# PCB_Timbangan.net
KiCad netlist of a schematic drawn in EasyEDA
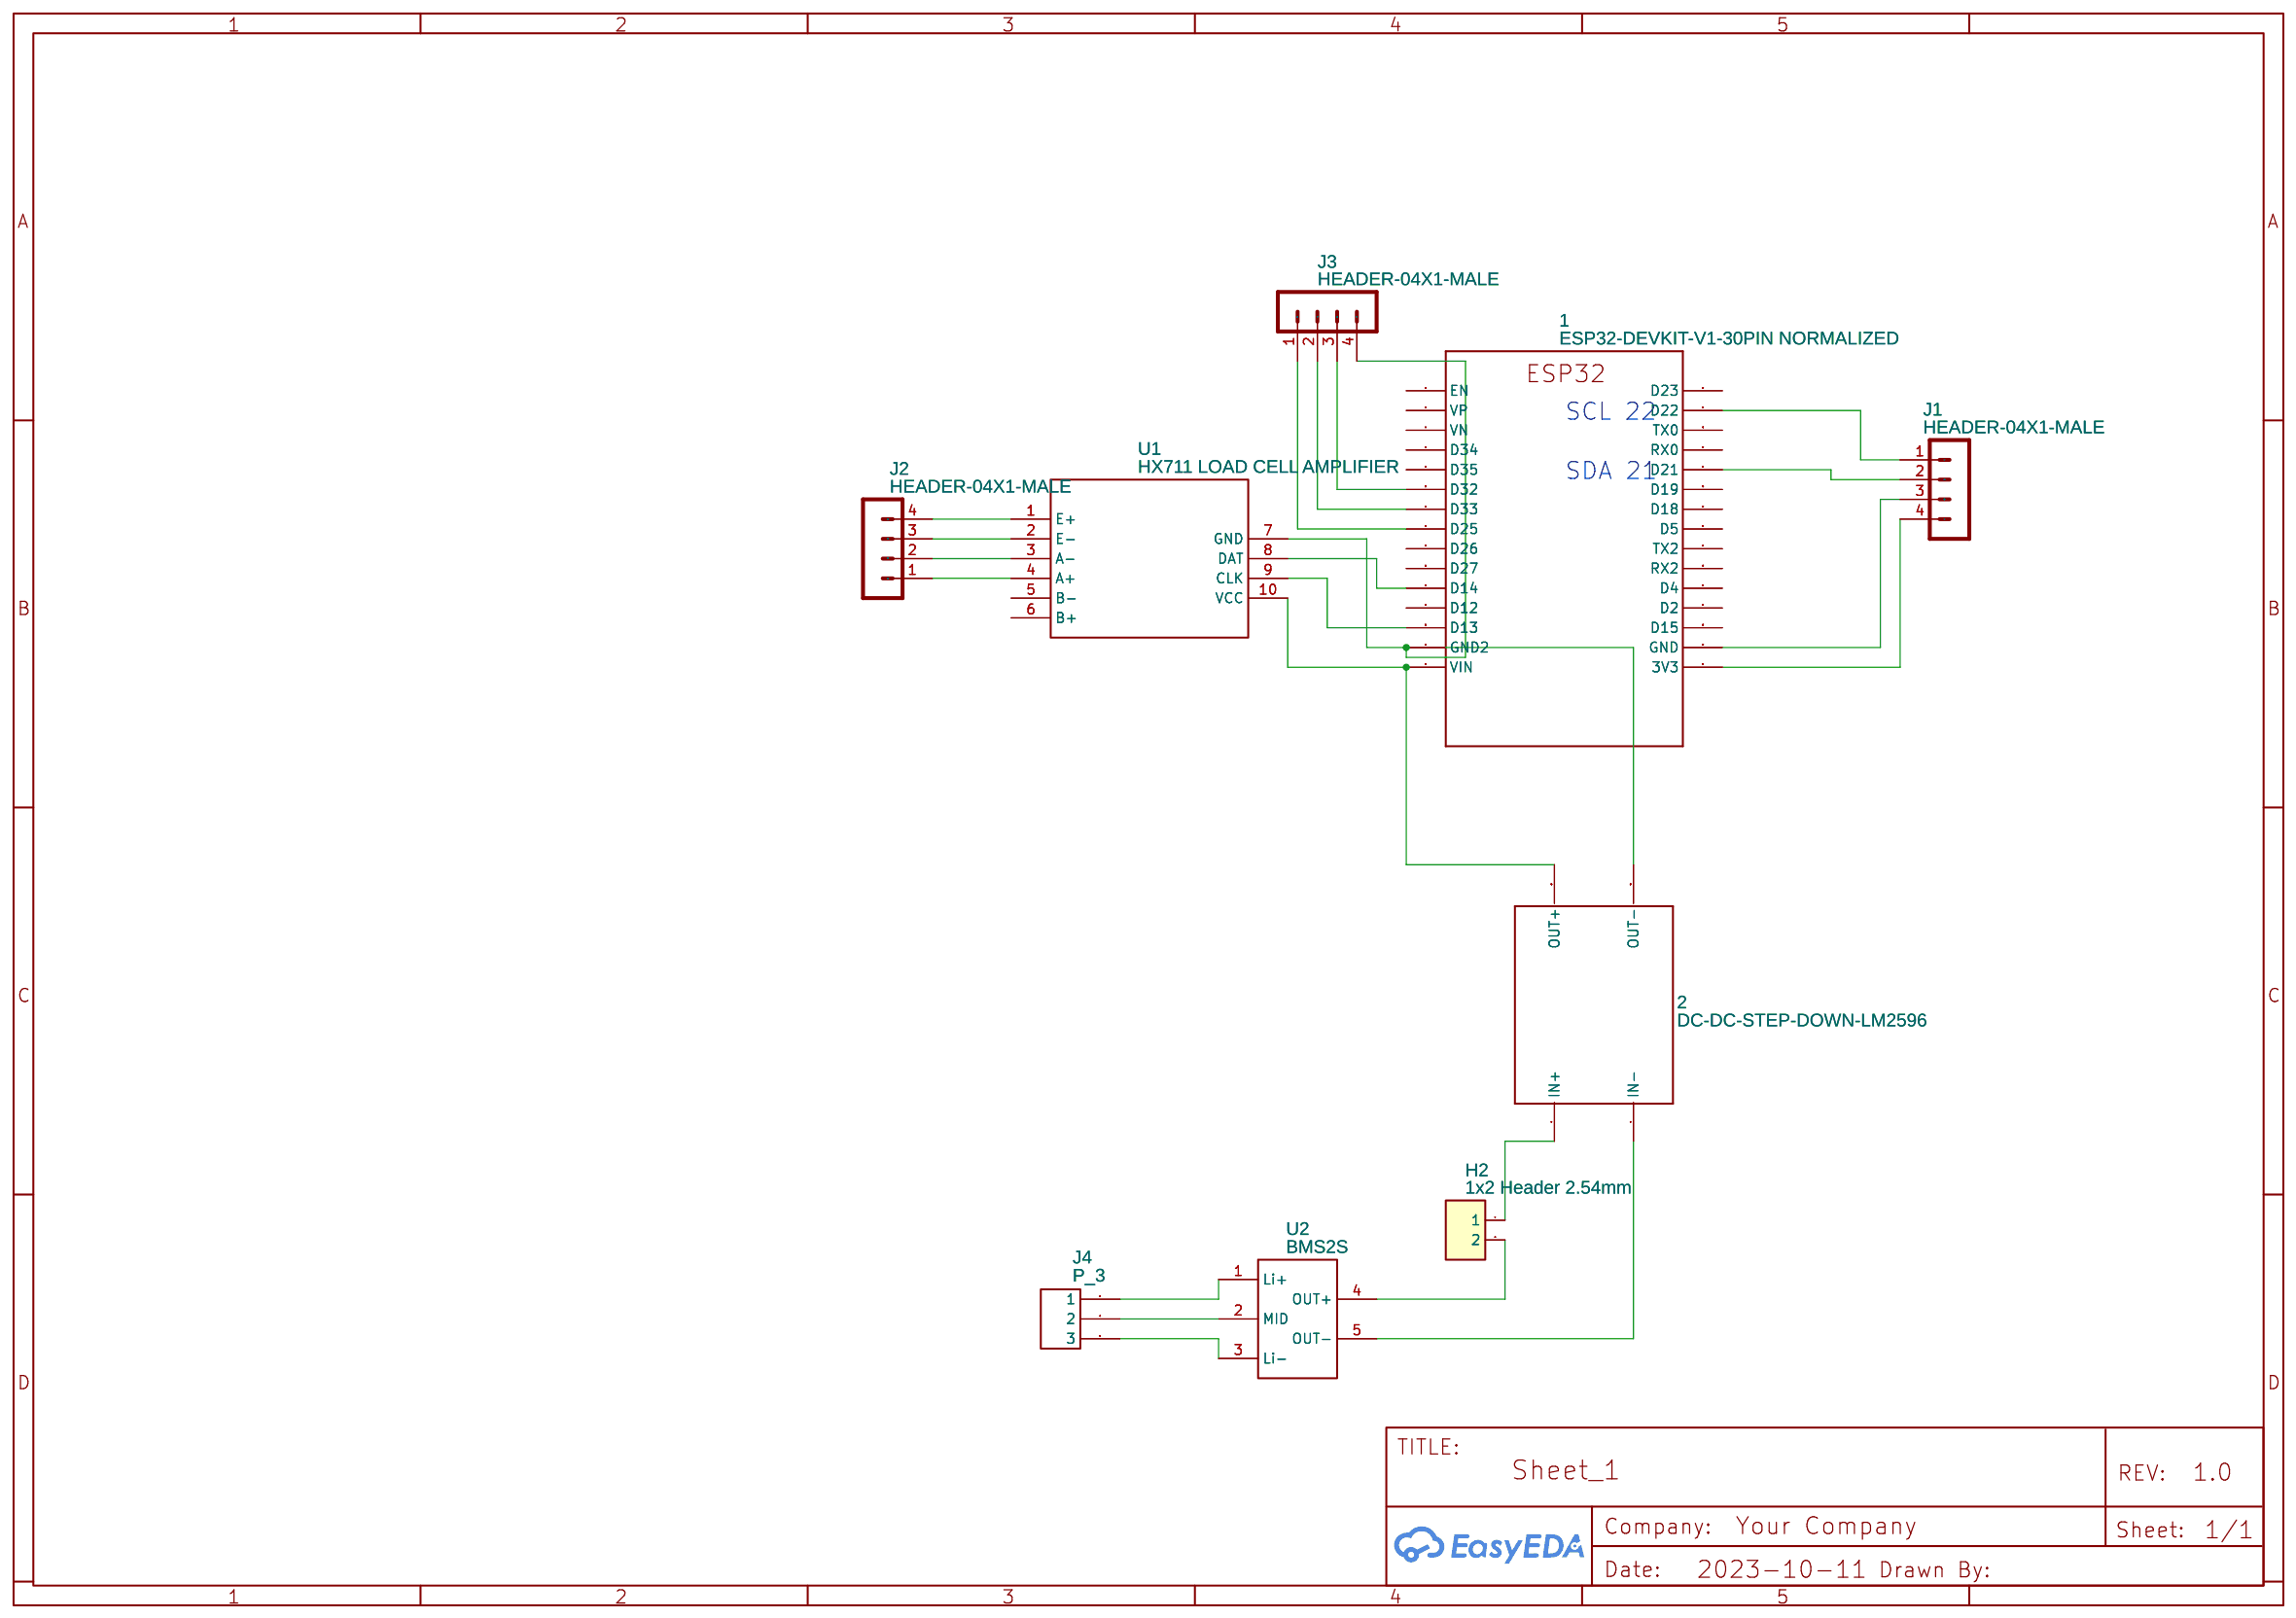
[diagram p0: schematic sheet]

(export (version "E")
  (design (tool "Eeschema 10.0.6"))
  (components
    (comp (ref "1")
      (value "ESP32-DEVKIT-V1-30PIN NORMALIZED")
      (libsource (lib "") (part "ESP32-DEVKIT-V1-30PIN"))
    )
    (comp (ref "2") (value "DC-DC-STEP-DOWN-LM2596") (libsource (lib "") (part "DC-DC-STEP-DOWN-LM2596")))
    (comp (ref "H2")
      (value "1x2 Header 2.54mm")
      (fields (field (name "Manufacturer Part") "New SchematicLib"))
      (libsource (lib "") (part "1x2 Header 2.54mm"))
    )
    (comp (ref "J1") (value "HEADER-04X1-MALE") (libsource (lib "") (part "HEADER-04X1-MALE_2")))
    (comp (ref "J2") (value "HEADER-04X1-MALE") (libsource (lib "") (part "HEADER-04X1-MALE_1")))
    (comp (ref "J3") (value "HEADER-04X1-MALE") (libsource (lib "") (part "HEADER-04X1-MALE")))
    (comp (ref "J4") (value "P_3") (libsource (lib "") (part "P_3")))
    (comp (ref "U1")
      (value "HX711 LOAD CELL AMPLIFIER")
      (libsource (lib "") (part "HX711 LOAD CELL AMPLIFIER"))
    )
    (comp (ref "U2") (value "BMS2S") (libsource (lib "") (part "BMS2S")))
  )
  (nets
    (net (code "1") (name "Net-(1-Pad3V3)") (class "Default")
      (node (ref "1") (pin "3V3") (pinfunction "3V3_3V3") (pintype "unspecified"))
      (node (ref "J1") (pin "4") (pinfunction "4_4") (pintype "unspecified"))
    )
    (net (code "2") (name "Net-(1-PadD21)") (class "Default")
      (node (ref "1") (pin "D21") (pinfunction "D21_D21") (pintype "unspecified"))
      (node (ref "J1") (pin "2") (pinfunction "2_2") (pintype "unspecified"))
    )
    (net (code "3") (name "Net-(1-PadD22)") (class "Default")
      (node (ref "1") (pin "D22") (pinfunction "D22_D22") (pintype "unspecified"))
      (node (ref "J1") (pin "1") (pinfunction "1_1") (pintype "unspecified"))
    )
    (net (code "4") (name "Net-(1-PadD25)") (class "Default")
      (node (ref "1") (pin "D25") (pinfunction "D25_D25") (pintype "unspecified"))
      (node (ref "J3") (pin "1") (pinfunction "1_1") (pintype "unspecified"))
    )
    (net (code "5") (name "Net-(1-PadD32)") (class "Default")
      (node (ref "1") (pin "D32") (pinfunction "D32_D32") (pintype "unspecified"))
      (node (ref "J3") (pin "3") (pinfunction "3_3") (pintype "unspecified"))
    )
    (net (code "6") (name "Net-(1-PadD33)") (class "Default")
      (node (ref "1") (pin "D33") (pinfunction "D33_D33") (pintype "unspecified"))
      (node (ref "J3") (pin "2") (pinfunction "2_2") (pintype "unspecified"))
    )
    (net (code "7") (name "Net-(1-PadGND)") (class "Default")
      (node (ref "1") (pin "GND") (pinfunction "GND_GND") (pintype "unspecified"))
      (node (ref "J1") (pin "3") (pinfunction "3_3") (pintype "unspecified"))
    )
    (net (code "8") (name "Net-(2-PadIN+)") (class "Default")
      (node (ref "2") (pin "IN+") (pinfunction "IN+_IN+") (pintype "bidirectional"))
      (node (ref "H2") (pin "1") (pinfunction "1_1") (pintype "unspecified"))
    )
    (net (code "9") (name "Net-(U1-A+)") (class "Default")
      (node (ref "J2") (pin "1") (pinfunction "1_1") (pintype "unspecified"))
      (node (ref "U1") (pin "4") (pinfunction "A+_4") (pintype "unspecified"))
    )
    (net (code "10") (name "Net-(U1-A-)") (class "Default")
      (node (ref "J2") (pin "2") (pinfunction "2_2") (pintype "unspecified"))
      (node (ref "U1") (pin "3") (pinfunction "A-_3") (pintype "unspecified"))
    )
    (net (code "11") (name "Net-(U1-CLK)") (class "Default")
      (node (ref "1") (pin "D13") (pinfunction "D13_D13") (pintype "unspecified"))
      (node (ref "U1") (pin "9") (pinfunction "CLK_9") (pintype "unspecified"))
    )
    (net (code "12") (name "Net-(U1-DAT)") (class "Default")
      (node (ref "1") (pin "D14") (pinfunction "D14_D14") (pintype "unspecified"))
      (node (ref "U1") (pin "8") (pinfunction "DAT_8") (pintype "unspecified"))
    )
    (net (code "13") (name "Net-(U1-E+)") (class "Default")
      (node (ref "J2") (pin "4") (pinfunction "4_4") (pintype "unspecified"))
      (node (ref "U1") (pin "1") (pinfunction "E+_1") (pintype "unspecified"))
    )
    (net (code "14") (name "Net-(U1-E-)") (class "Default")
      (node (ref "J2") (pin "3") (pinfunction "3_3") (pintype "unspecified"))
      (node (ref "U1") (pin "2") (pinfunction "E-_2") (pintype "unspecified"))
    )
    (net (code "15") (name "Net-(U1-GND)") (class "Default")
      (node (ref "1") (pin "GND2") (pinfunction "GND2_GND2") (pintype "unspecified"))
      (node (ref "2") (pin "OUT-") (pinfunction "OUT-_OUT-") (pintype "bidirectional"))
      (node (ref "J3") (pin "4") (pinfunction "4_4") (pintype "unspecified"))
      (node (ref "U1") (pin "7") (pinfunction "GND_7") (pintype "unspecified"))
    )
    (net (code "16") (name "Net-(U1-VCC)") (class "Default")
      (node (ref "1") (pin "VIN") (pinfunction "VIN_VIN") (pintype "unspecified"))
      (node (ref "2") (pin "OUT+") (pinfunction "OUT+_OUT+") (pintype "bidirectional"))
      (node (ref "U1") (pin "10") (pinfunction "VCC_10") (pintype "unspecified"))
    )
    (net (code "17") (name "Net-(U2-Li+)") (class "Default")
      (node (ref "J4") (pin "1") (pinfunction "1_1") (pintype "unspecified"))
      (node (ref "U2") (pin "1") (pinfunction "Li+_1") (pintype "unspecified"))
    )
    (net (code "18") (name "Net-(U2-Li-)") (class "Default")
      (node (ref "J4") (pin "3") (pinfunction "3_3") (pintype "unspecified"))
      (node (ref "U2") (pin "3") (pinfunction "Li-_3") (pintype "unspecified"))
    )
    (net (code "19") (name "Net-(U2-MID)") (class "Default")
      (node (ref "J4") (pin "2") (pinfunction "2_2") (pintype "unspecified"))
      (node (ref "U2") (pin "2") (pinfunction "MID_2") (pintype "unspecified"))
    )
    (net (code "20") (name "Net-(U2-OUT+)") (class "Default")
      (node (ref "H2") (pin "2") (pinfunction "2_2") (pintype "unspecified"))
      (node (ref "U2") (pin "4") (pinfunction "OUT+_4") (pintype "unspecified"))
    )
    (net (code "21") (name "Net-(U2-OUT-)") (class "Default")
      (node (ref "2") (pin "IN-") (pinfunction "IN-_IN-") (pintype "bidirectional"))
      (node (ref "U2") (pin "5") (pinfunction "OUT-_5") (pintype "unspecified"))
    )
    (net (code "22") (name "unconnected-(1-PadD2)") (class "Default")
      (node (ref "1") (pin "D2") (pinfunction "D2_D2") (pintype "unspecified"))
    )
    (net (code "23") (name "unconnected-(1-PadD4)") (class "Default")
      (node (ref "1") (pin "D4") (pinfunction "D4_D4") (pintype "unspecified"))
    )
    (net (code "24") (name "unconnected-(1-PadD5)") (class "Default")
      (node (ref "1") (pin "D5") (pinfunction "D5_D5") (pintype "unspecified"))
    )
    (net (code "25") (name "unconnected-(1-PadD12)") (class "Default")
      (node (ref "1") (pin "D12") (pinfunction "D12_D12") (pintype "unspecified"))
    )
    (net (code "26") (name "unconnected-(1-PadD15)") (class "Default")
      (node (ref "1") (pin "D15") (pinfunction "D15_D15") (pintype "unspecified"))
    )
    (net (code "27") (name "unconnected-(1-PadD18)") (class "Default")
      (node (ref "1") (pin "D18") (pinfunction "D18_D18") (pintype "unspecified"))
    )
    (net (code "28") (name "unconnected-(1-PadD19)") (class "Default")
      (node (ref "1") (pin "D19") (pinfunction "D19_D19") (pintype "unspecified"))
    )
    (net (code "29") (name "unconnected-(1-PadD23)") (class "Default")
      (node (ref "1") (pin "D23") (pinfunction "D23_D23") (pintype "unspecified"))
    )
    (net (code "30") (name "unconnected-(1-PadD26)") (class "Default")
      (node (ref "1") (pin "D26") (pinfunction "D26_D26") (pintype "unspecified"))
    )
    (net (code "31") (name "unconnected-(1-PadD27)") (class "Default")
      (node (ref "1") (pin "D27") (pinfunction "D27_D27") (pintype "unspecified"))
    )
    (net (code "32") (name "unconnected-(1-PadD34)") (class "Default")
      (node (ref "1") (pin "D34") (pinfunction "D34_D34") (pintype "unspecified"))
    )
    (net (code "33") (name "unconnected-(1-PadD35)") (class "Default")
      (node (ref "1") (pin "D35") (pinfunction "D35_D35") (pintype "unspecified"))
    )
    (net (code "34") (name "unconnected-(1-PadEN)") (class "Default")
      (node (ref "1") (pin "EN") (pinfunction "EN_EN") (pintype "unspecified"))
    )
    (net (code "35") (name "unconnected-(1-PadRX0)") (class "Default")
      (node (ref "1") (pin "RX0") (pinfunction "RX0_RX0") (pintype "unspecified"))
    )
    (net (code "36") (name "unconnected-(1-PadRX2)") (class "Default")
      (node (ref "1") (pin "RX2") (pinfunction "RX2_RX2") (pintype "unspecified"))
    )
    (net (code "37") (name "unconnected-(1-PadTX0)") (class "Default")
      (node (ref "1") (pin "TX0") (pinfunction "TX0_TX0") (pintype "unspecified"))
    )
    (net (code "38") (name "unconnected-(1-PadTX2)") (class "Default")
      (node (ref "1") (pin "TX2") (pinfunction "TX2_TX2") (pintype "unspecified"))
    )
    (net (code "39") (name "unconnected-(1-PadVN)") (class "Default")
      (node (ref "1") (pin "VN") (pinfunction "VN_VN") (pintype "unspecified"))
    )
    (net (code "40") (name "unconnected-(1-PadVP)") (class "Default")
      (node (ref "1") (pin "VP") (pinfunction "VP_VP") (pintype "unspecified"))
    )
    (net (code "41") (name "unconnected-(U1-B+-Pad6)") (class "Default")
      (node (ref "U1") (pin "6") (pinfunction "B+_6") (pintype "unspecified"))
    )
    (net (code "42") (name "unconnected-(U1-B--Pad5)") (class "Default")
      (node (ref "U1") (pin "5") (pinfunction "B-_5") (pintype "unspecified"))
    )
  )
)
